# thrust_RP2040.net
KiCad netlist of a schematic drawn in Altium Designer
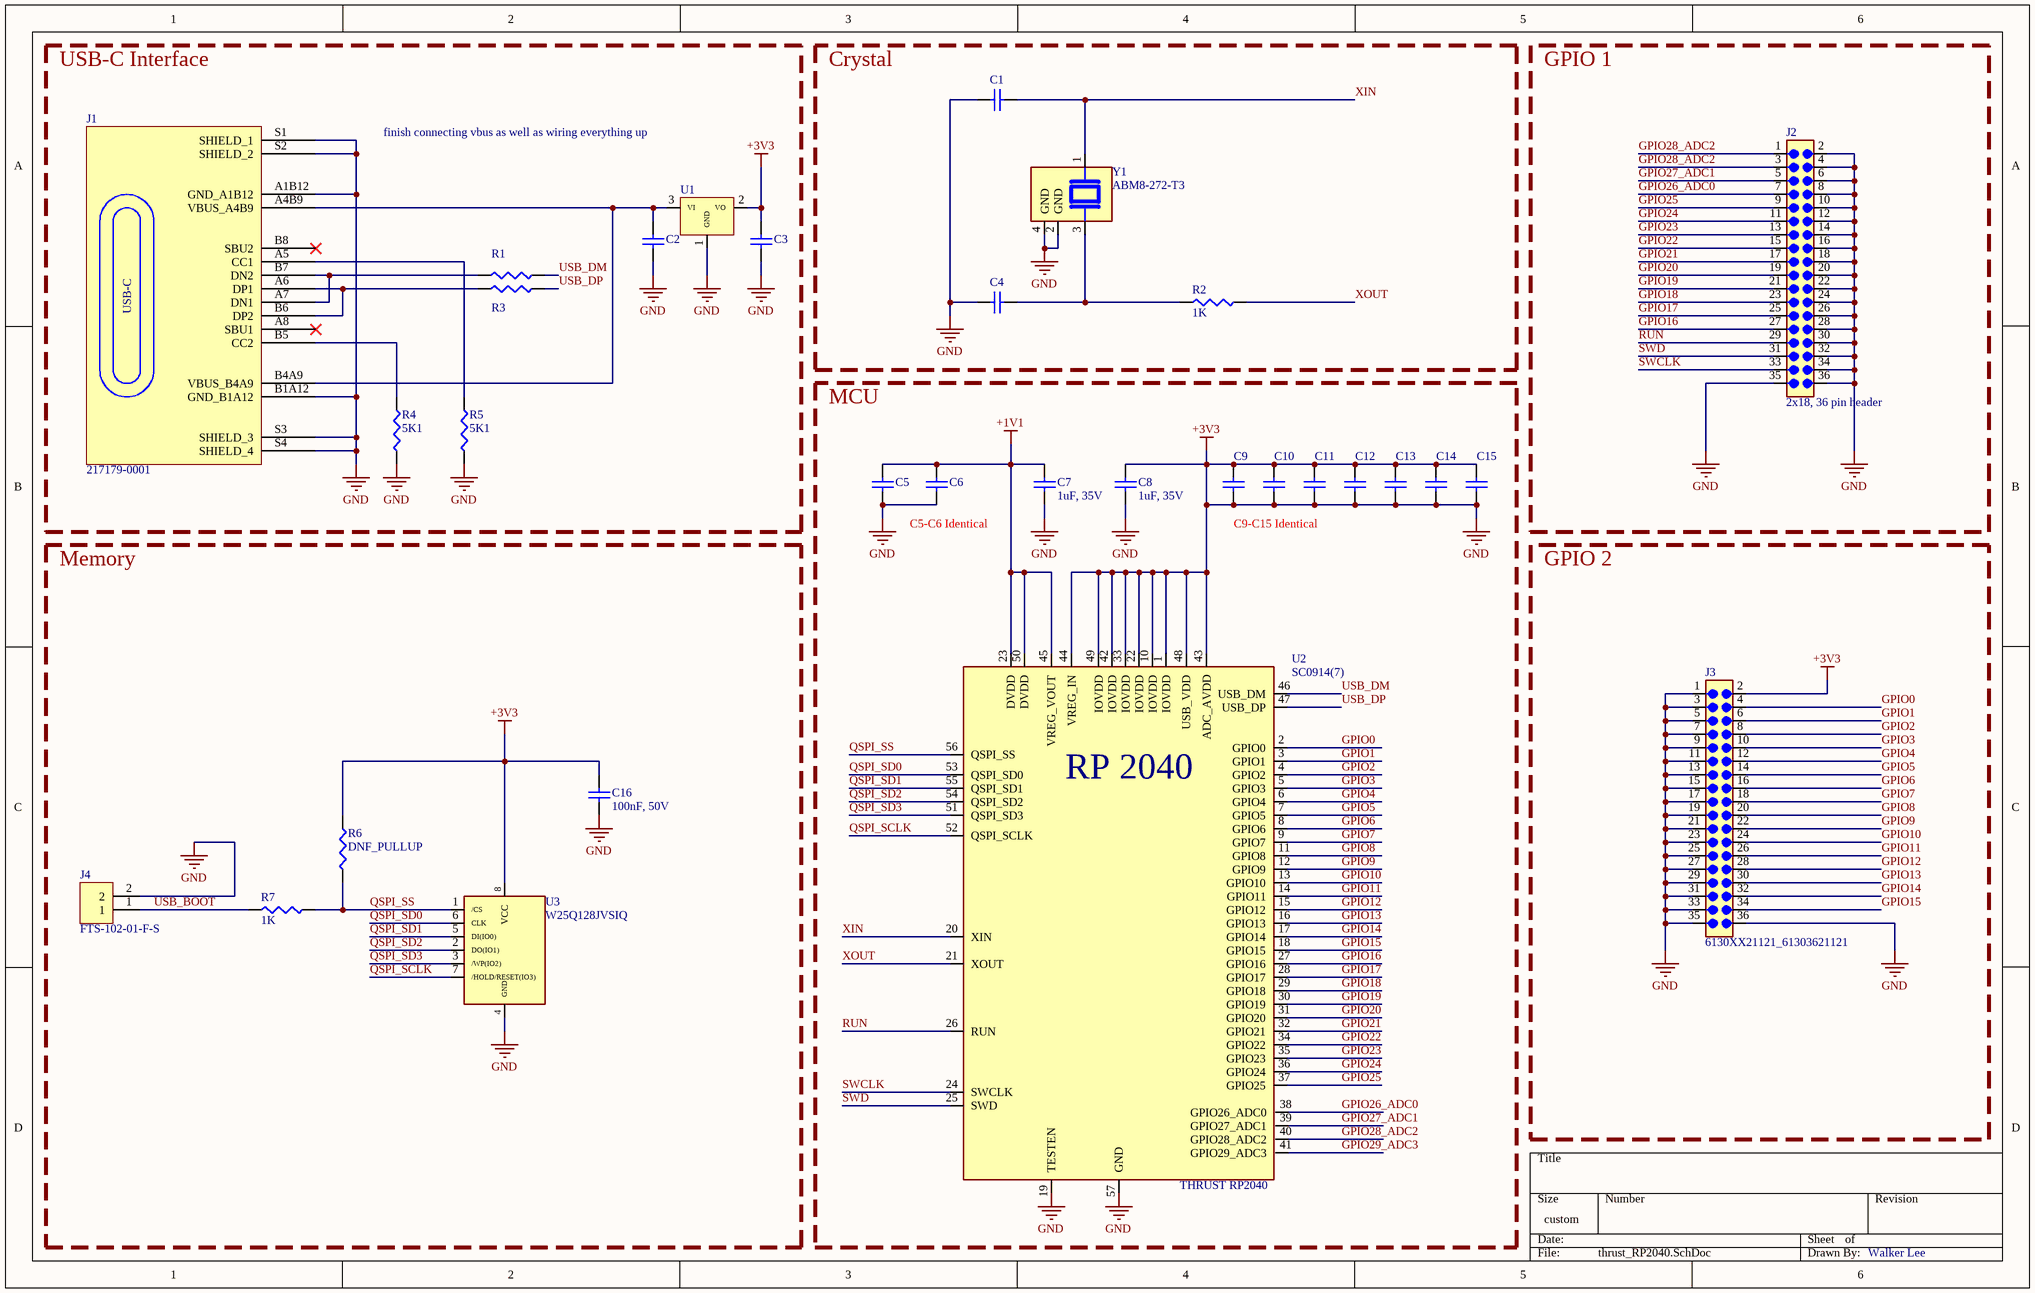
[diagram p0: thrust_RP2040.SchDoc]

(export (version "E")
  (design (tool "Eeschema 10.0.6"))
  (components
    (comp (ref "C1")
      (value "CL05C150JB5NNNC")
      (description "CAP CER 15PF 50V C0G/NP0 0402")
      (fields (field (name "MANUFACTURER") "Samsung Electro-Mechanics") (field (name "TOLERANCE") "5%"))
      (libsource (lib "thrust_obc") (part "CL05C150JB5NNNC"))
    )
    (comp (ref "C2")
      (value "10uF, 10V")
      (footprint "CAPC1005X55N")
      (description "CAP CER 10UF 10V X5R 0402")
      (fields
        (field (name "MANUFACTURER") "Samsung")
        (field (name "MANUFACTURER PART NUMBER") "CL05A106MP8NUB8")
      )
      (libsource (lib "thrust_obc") (part "CL05A106MP8NUB8"))
    )
    (comp (ref "C3")
      (value "10uF, 10V")
      (footprint "CAPC1005X55N")
      (description "CAP CER 10UF 10V X5R 0402")
      (fields
        (field (name "MANUFACTURER") "Samsung")
        (field (name "MANUFACTURER PART NUMBER") "CL05A106MP8NUB8")
      )
      (libsource (lib "thrust_obc") (part "CL05A106MP8NUB8"))
    )
    (comp (ref "C4")
      (value "CL05C150JB5NNNC")
      (description "CAP CER 15PF 50V C0G/NP0 0402")
      (fields (field (name "MANUFACTURER") "Samsung Electro-Mechanics") (field (name "TOLERANCE") "5%"))
      (libsource (lib "thrust_obc") (part "CL05C150JB5NNNC"))
    )
    (comp (ref "C5")
      (value "100nF, 50V")
      (footprint "CAPC1005X55N")
      (description "50V 100nF X7R 10% 0402 Multilayer Ceramic Capacitors MLCC - SMD/SMT ROHS")
      (fields
        (field (name "MANUFACTURER") "Samsung")
        (field (name "MANUFACTURER PART NUMBER") "CL05B104KB54PNC")
      )
      (libsource (lib "thrust_obc") (part "CL05B104KB54PNC"))
    )
    (comp (ref "C6")
      (value "100nF, 50V")
      (footprint "CAPC1005X55N")
      (description "50V 100nF X7R 10% 0402 Multilayer Ceramic Capacitors MLCC - SMD/SMT ROHS")
      (fields
        (field (name "MANUFACTURER") "Samsung")
        (field (name "MANUFACTURER PART NUMBER") "CL05B104KB54PNC")
      )
      (libsource (lib "thrust_obc") (part "CL05B104KB54PNC"))
    )
    (comp (ref "C7")
      (value "1uF, 35V")
      (footprint "CAPC1005X55N")
      (description "CAP CER 1UF 35V X5R 0402")
      (fields
        (field (name "MANUFACTURER") "Samsung")
        (field (name "MANUFACTURER PART NUMBER") "CL05A105KL5NRNC")
      )
      (libsource (lib "thrust_obc") (part "CL05A105KL5NRNC"))
    )
    (comp (ref "C8")
      (value "1uF, 35V")
      (footprint "CAPC1005X55N")
      (description "CAP CER 1UF 35V X5R 0402")
      (fields
        (field (name "MANUFACTURER") "Samsung")
        (field (name "MANUFACTURER PART NUMBER") "CL05A105KL5NRNC")
      )
      (libsource (lib "thrust_obc") (part "CL05A105KL5NRNC"))
    )
    (comp (ref "C9")
      (value "100nF, 50V")
      (footprint "CAPC1005X55N")
      (description "50V 100nF X7R 10% 0402 Multilayer Ceramic Capacitors MLCC - SMD/SMT ROHS")
      (fields
        (field (name "MANUFACTURER") "Samsung")
        (field (name "MANUFACTURER PART NUMBER") "CL05B104KB54PNC")
      )
      (libsource (lib "thrust_obc") (part "CL05B104KB54PNC"))
    )
    (comp (ref "C10")
      (value "100nF, 50V")
      (footprint "CAPC1005X55N")
      (description "50V 100nF X7R 10% 0402 Multilayer Ceramic Capacitors MLCC - SMD/SMT ROHS")
      (fields
        (field (name "MANUFACTURER") "Samsung")
        (field (name "MANUFACTURER PART NUMBER") "CL05B104KB54PNC")
      )
      (libsource (lib "thrust_obc") (part "CL05B104KB54PNC"))
    )
    (comp (ref "C11")
      (value "100nF, 50V")
      (footprint "CAPC1005X55N")
      (description "50V 100nF X7R 10% 0402 Multilayer Ceramic Capacitors MLCC - SMD/SMT ROHS")
      (fields
        (field (name "MANUFACTURER") "Samsung")
        (field (name "MANUFACTURER PART NUMBER") "CL05B104KB54PNC")
      )
      (libsource (lib "thrust_obc") (part "CL05B104KB54PNC"))
    )
    (comp (ref "C12")
      (value "100nF, 50V")
      (footprint "CAPC1005X55N")
      (description "50V 100nF X7R 10% 0402 Multilayer Ceramic Capacitors MLCC - SMD/SMT ROHS")
      (fields
        (field (name "MANUFACTURER") "Samsung")
        (field (name "MANUFACTURER PART NUMBER") "CL05B104KB54PNC")
      )
      (libsource (lib "thrust_obc") (part "CL05B104KB54PNC"))
    )
    (comp (ref "C13")
      (value "100nF, 50V")
      (footprint "CAPC1005X55N")
      (description "50V 100nF X7R 10% 0402 Multilayer Ceramic Capacitors MLCC - SMD/SMT ROHS")
      (fields
        (field (name "MANUFACTURER") "Samsung")
        (field (name "MANUFACTURER PART NUMBER") "CL05B104KB54PNC")
      )
      (libsource (lib "thrust_obc") (part "CL05B104KB54PNC"))
    )
    (comp (ref "C14")
      (value "100nF, 50V")
      (footprint "CAPC1005X55N")
      (description "50V 100nF X7R 10% 0402 Multilayer Ceramic Capacitors MLCC - SMD/SMT ROHS")
      (fields
        (field (name "MANUFACTURER") "Samsung")
        (field (name "MANUFACTURER PART NUMBER") "CL05B104KB54PNC")
      )
      (libsource (lib "thrust_obc") (part "CL05B104KB54PNC"))
    )
    (comp (ref "C15")
      (value "100nF, 50V")
      (footprint "CAPC1005X55N")
      (description "50V 100nF X7R 10% 0402 Multilayer Ceramic Capacitors MLCC - SMD/SMT ROHS")
      (fields
        (field (name "MANUFACTURER") "Samsung")
        (field (name "MANUFACTURER PART NUMBER") "CL05B104KB54PNC")
      )
      (libsource (lib "thrust_obc") (part "CL05B104KB54PNC"))
    )
    (comp (ref "C16")
      (value "100nF, 50V")
      (footprint "CAPC1005X55N")
      (description "50V 100nF X7R 10% 0402 Multilayer Ceramic Capacitors MLCC - SMD/SMT ROHS")
      (fields
        (field (name "MANUFACTURER") "Samsung")
        (field (name "MANUFACTURER PART NUMBER") "CL05B104KB54PNC")
      )
      (libsource (lib "thrust_obc") (part "CL05B104KB54PNC"))
    )
    (comp (ref "J1")
      (value "217179-0001")
      (footprint "FP-2171790001-MFG")
      (description "CONN RCP USB2.0 TYP C 24P SMD RA")
      (fields (field (name "MANUFACTURER") "Molex") (field (name "LCSC PART NUMBER") "C3197684"))
      (libsource (lib "thrust_obc") (part "217179-0001"))
    )
    (comp (ref "J2")
      (value "2x18, 36 pin header")
      (footprint "61303621121")
      (description "36 pins, dual Row , straight, gold plating")
      (fields (field (name "MF") "Wurth Electronics") (field (name "MP") "61303621121"))
      (libsource (lib "thrust_obc") (part "6130XX21121_61303621121"))
    )
    (comp (ref "J3")
      (value "6130XX21121_61303621121")
      (footprint "61303621121")
      (description "36 pins, dual Row , straight, gold plating")
      (fields (field (name "MF") "Wurth Electronics") (field (name "MP") "61303621121"))
      (libsource (lib "thrust_obc") (part "6130XX21121_61303621121"))
    )
    (comp (ref "J4")
      (value "FTS-102-01-F-S")
      (description "CONN HEADER VERT 2POS 1.27MM")
      (fields (field (name "MANUFACTURER") "Samtec") (field (name "LCSC PART NUMBER") "C6045317"))
      (libsource (lib "thrust_obc") (part "FTS-102-01-F-S"))
    )
    (comp (ref "R1")
      (value "27R")
      (footprint "RESC1005X37N")
      (description "RES 27 OHM 1% 1/16W 0402")
      (fields
        (field (name "MANUFACTURER") "Yageo")
        (field (name "MANUFACTURER PART NUMBER") "RC0402FR-0727RL")
      )
      (libsource (lib "thrust_obc") (part "RC0402FR-0727RL"))
    )
    (comp (ref "R2")
      (value "1K")
      (footprint "RESC1005X37N")
      (description "RES 1K OHM 1% 1/16W 0402")
      (fields
        (field (name "MANUFACTURER") "Yageo")
        (field (name "MANUFACTURER PART NUMBER") "RC0402FR-071KL")
      )
      (libsource (lib "thrust_obc") (part "RC0402FR-071KL"))
    )
    (comp (ref "R3")
      (value "27R")
      (footprint "RESC1005X37N")
      (description "RES 27 OHM 1% 1/16W 0402")
      (fields
        (field (name "MANUFACTURER") "Yageo")
        (field (name "MANUFACTURER PART NUMBER") "RC0402FR-0727RL")
      )
      (libsource (lib "thrust_obc") (part "RC0402FR-0727RL"))
    )
    (comp (ref "R4")
      (value "5K1")
      (footprint "RESC1005X37N")
      (description "RES SMD 5.1K OHM 1% 1/16W 0402")
      (fields
        (field (name "MANUFACTURER") "Yageo")
        (field (name "MANUFACTURER PART NUMBER") "AC0402FR-075K1L")
      )
      (libsource (lib "thrust_obc") (part "AC0402FR-075K1L"))
    )
    (comp (ref "R5")
      (value "5K1")
      (footprint "RESC1005X37N")
      (description "RES SMD 5.1K OHM 1% 1/16W 0402")
      (fields
        (field (name "MANUFACTURER") "Yageo")
        (field (name "MANUFACTURER PART NUMBER") "AC0402FR-075K1L")
      )
      (libsource (lib "thrust_obc") (part "AC0402FR-075K1L"))
    )
    (comp (ref "R6")
      (value "DNF_PULLUP")
      (footprint "RESC1005X37N")
      (description "Generic 0402 Resistor - DO NOT POPULATE")
      (fields
        (field (name "MANUFACTURER") "Yageo")
        (field (name "MANUFACTURER PART NUMBER") "RC0402FR-071KL")
      )
      (libsource (lib "thrust_obc") (part "RC0402FR-071KL_1"))
    )
    (comp (ref "R7")
      (value "1K")
      (footprint "RESC1005X37N")
      (description "RES 1K OHM 1% 1/16W 0402")
      (fields
        (field (name "MANUFACTURER") "Yageo")
        (field (name "MANUFACTURER PART NUMBER") "RC0402FR-071KL")
      )
      (libsource (lib "thrust_obc") (part "RC0402FR-071KL"))
    )
    (comp (ref "U1")
      (value "NCP1117ST33T3G")
      (description "IC REG LINEAR 3.3V 1A SOT-223")
      (fields (field (name "MANUFACTURER") "onsemi") (field (name "TOLERANCE") "1%"))
      (libsource (lib "thrust_obc") (part "NCP1117ST33T3G"))
    )
    (comp (ref "U2")
      (value "SC0914(7)")
      (description "RISC Microcontroller, FLASH, Cortex-M0+ CPU, 133MHz, CMOS")
      (fields (field (name "MANUFACTURER") "Raspberry Pi") (field (name "LCSC PART NUMBER") "C6472266"))
      (libsource (lib "thrust_obc") (part "SC0914(7)"))
    )
    (comp (ref "U3")
      (value "W25Q128JVSIQ")
      (footprint "SOIC127P790X216-8N")
      (description "FLASH - NOR Memory IC 128Mb (16M x 8) SPI - Quad I/O, QPI, DTR 133 MHz 8-SOIC")
      (fields (field (name "MF") "Winbond Electronics") (field (name "LCSC PART NUMBER") "C97521"))
      (libsource (lib "thrust_obc") (part "W25Q128JVSIQ"))
    )
    (comp (ref "Y1")
      (value "ABM8-272-T3")
      (footprint "XTAL_ABM8-272-T3")
      (description "12 MHz Â±30ppm Crystal 10pF 50 Ohms 4-SMD, No Lead")
      (fields (field (name "MF") "ABRACON") (field (name "LCSC PART NUMBER") "C20625731"))
      (libsource (lib "thrust_obc") (part "ABM8-272-T3"))
    )
  )
  (nets
    (net (code "1") (name "+1V1") (class "Default")
      (node (ref "C5") (pin "2") (pinfunction "2_2") (pintype "passive"))
      (node (ref "C6") (pin "2") (pinfunction "2_2") (pintype "passive"))
      (node (ref "C7") (pin "2") (pinfunction "2_2") (pintype "passive"))
      (node (ref "U2") (pin "23") (pinfunction "DVDD_23") (pintype "passive"))
      (node (ref "U2") (pin "45") (pinfunction "VREG_VOUT_45") (pintype "passive"))
      (node (ref "U2") (pin "50") (pinfunction "DVDD_50") (pintype "passive"))
    )
    (net (code "2") (name "+3V3") (class "Default")
      (node (ref "C1") (pin "1") (pinfunction "1_1") (pintype "passive"))
      (node (ref "C10") (pin "1") (pinfunction "1_1") (pintype "passive"))
      (node (ref "C10") (pin "2") (pinfunction "2_2") (pintype "passive"))
      (node (ref "C11") (pin "1") (pinfunction "1_1") (pintype "passive"))
      (node (ref "C11") (pin "2") (pinfunction "2_2") (pintype "passive"))
      (node (ref "C12") (pin "1") (pinfunction "1_1") (pintype "passive"))
      (node (ref "C12") (pin "2") (pinfunction "2_2") (pintype "passive"))
      (node (ref "C13") (pin "1") (pinfunction "1_1") (pintype "passive"))
      (node (ref "C13") (pin "2") (pinfunction "2_2") (pintype "passive"))
      (node (ref "C14") (pin "1") (pinfunction "1_1") (pintype "passive"))
      (node (ref "C14") (pin "2") (pinfunction "2_2") (pintype "passive"))
      (node (ref "C15") (pin "1") (pinfunction "1_1") (pintype "passive"))
      (node (ref "C15") (pin "2") (pinfunction "2_2") (pintype "passive"))
      (node (ref "C16") (pin "1") (pinfunction "1_1") (pintype "passive"))
      (node (ref "C16") (pin "2") (pinfunction "2_2") (pintype "passive"))
      (node (ref "C2") (pin "1") (pinfunction "1_1") (pintype "passive"))
      (node (ref "C3") (pin "1") (pinfunction "1_1") (pintype "passive"))
      (node (ref "C3") (pin "2") (pinfunction "2_2") (pintype "passive"))
      (node (ref "C4") (pin "1") (pinfunction "1_1") (pintype "passive"))
      (node (ref "C5") (pin "1") (pinfunction "1_1") (pintype "passive"))
      (node (ref "C6") (pin "1") (pinfunction "1_1") (pintype "passive"))
      (node (ref "C7") (pin "1") (pinfunction "1_1") (pintype "passive"))
      (node (ref "C8") (pin "1") (pinfunction "1_1") (pintype "passive"))
      (node (ref "C8") (pin "2") (pinfunction "2_2") (pintype "passive"))
      (node (ref "C9") (pin "1") (pinfunction "1_1") (pintype "passive"))
      (node (ref "C9") (pin "2") (pinfunction "2_2") (pintype "passive"))
      (node (ref "J1") (pin "A1B12") (pinfunction "GND_A1B12_A1B12") (pintype "passive"))
      (node (ref "J1") (pin "B1A12") (pinfunction "GND_B1A12_B1A12") (pintype "passive"))
      (node (ref "J1") (pin "S1") (pinfunction "SHIELD_1_S1") (pintype "passive"))
      (node (ref "J1") (pin "S2") (pinfunction "SHIELD_2_S2") (pintype "passive"))
      (node (ref "J1") (pin "S3") (pinfunction "SHIELD_3_S3") (pintype "passive"))
      (node (ref "J1") (pin "S4") (pinfunction "SHIELD_4_S4") (pintype "passive"))
      (node (ref "J2") (pin "10") (pinfunction "10_10") (pintype "passive"))
      (node (ref "J2") (pin "12") (pinfunction "12_12") (pintype "passive"))
      (node (ref "J2") (pin "14") (pinfunction "14_14") (pintype "passive"))
      (node (ref "J2") (pin "16") (pinfunction "16_16") (pintype "passive"))
      (node (ref "J2") (pin "18") (pinfunction "18_18") (pintype "passive"))
      (node (ref "J2") (pin "2") (pinfunction "2_2") (pintype "passive"))
      (node (ref "J2") (pin "20") (pinfunction "20_20") (pintype "passive"))
      (node (ref "J2") (pin "22") (pinfunction "22_22") (pintype "passive"))
      (node (ref "J2") (pin "24") (pinfunction "24_24") (pintype "passive"))
      (node (ref "J2") (pin "26") (pinfunction "26_26") (pintype "passive"))
      (node (ref "J2") (pin "28") (pinfunction "28_28") (pintype "passive"))
      (node (ref "J2") (pin "30") (pinfunction "30_30") (pintype "passive"))
      (node (ref "J2") (pin "32") (pinfunction "32_32") (pintype "passive"))
      (node (ref "J2") (pin "34") (pinfunction "34_34") (pintype "passive"))
      (node (ref "J2") (pin "35") (pinfunction "35_35") (pintype "passive"))
      (node (ref "J2") (pin "36") (pinfunction "36_36") (pintype "passive"))
      (node (ref "J2") (pin "4") (pinfunction "4_4") (pintype "passive"))
      (node (ref "J2") (pin "6") (pinfunction "6_6") (pintype "passive"))
      (node (ref "J2") (pin "8") (pinfunction "8_8") (pintype "passive"))
      (node (ref "J3") (pin "1") (pinfunction "1_1") (pintype "passive"))
      (node (ref "J3") (pin "11") (pinfunction "11_11") (pintype "passive"))
      (node (ref "J3") (pin "13") (pinfunction "13_13") (pintype "passive"))
      (node (ref "J3") (pin "15") (pinfunction "15_15") (pintype "passive"))
      (node (ref "J3") (pin "17") (pinfunction "17_17") (pintype "passive"))
      (node (ref "J3") (pin "19") (pinfunction "19_19") (pintype "passive"))
      (node (ref "J3") (pin "2") (pinfunction "2_2") (pintype "passive"))
      (node (ref "J3") (pin "21") (pinfunction "21_21") (pintype "passive"))
      (node (ref "J3") (pin "23") (pinfunction "23_23") (pintype "passive"))
      (node (ref "J3") (pin "25") (pinfunction "25_25") (pintype "passive"))
      (node (ref "J3") (pin "27") (pinfunction "27_27") (pintype "passive"))
      (node (ref "J3") (pin "29") (pinfunction "29_29") (pintype "passive"))
      (node (ref "J3") (pin "3") (pinfunction "3_3") (pintype "passive"))
      (node (ref "J3") (pin "31") (pinfunction "31_31") (pintype "passive"))
      (node (ref "J3") (pin "33") (pinfunction "33_33") (pintype "passive"))
      (node (ref "J3") (pin "35") (pinfunction "35_35") (pintype "passive"))
      (node (ref "J3") (pin "36") (pinfunction "36_36") (pintype "passive"))
      (node (ref "J3") (pin "5") (pinfunction "5_5") (pintype "passive"))
      (node (ref "J3") (pin "7") (pinfunction "7_7") (pintype "passive"))
      (node (ref "J3") (pin "9") (pinfunction "9_9") (pintype "passive"))
      (node (ref "J4") (pin "2") (pinfunction "2_2") (pintype "passive"))
      (node (ref "R4") (pin "1") (pinfunction "1_1") (pintype "passive"))
      (node (ref "R5") (pin "1") (pinfunction "1_1") (pintype "passive"))
      (node (ref "R6") (pin "2") (pinfunction "2_2") (pintype "passive"))
      (node (ref "U1") (pin "1") (pinfunction "GND_1") (pintype "passive"))
      (node (ref "U1") (pin "2") (pinfunction "VO_2") (pintype "passive"))
      (node (ref "U2") (pin "1") (pinfunction "IOVDD_1") (pintype "passive"))
      (node (ref "U2") (pin "10") (pinfunction "IOVDD_10") (pintype "passive"))
      (node (ref "U2") (pin "19") (pinfunction "TESTEN_19") (pintype "passive"))
      (node (ref "U2") (pin "22") (pinfunction "IOVDD_22") (pintype "passive"))
      (node (ref "U2") (pin "33") (pinfunction "IOVDD_33") (pintype "passive"))
      (node (ref "U2") (pin "42") (pinfunction "IOVDD_42") (pintype "passive"))
      (node (ref "U2") (pin "43") (pinfunction "ADC_AVDD_43") (pintype "passive"))
      (node (ref "U2") (pin "44") (pinfunction "VREG_IN_44") (pintype "passive"))
      (node (ref "U2") (pin "48") (pinfunction "USB_VDD_48") (pintype "passive"))
      (node (ref "U2") (pin "49") (pinfunction "IOVDD_49") (pintype "passive"))
      (node (ref "U2") (pin "57") (pinfunction "GND_57") (pintype "passive"))
      (node (ref "U3") (pin "4") (pinfunction "GND_4") (pintype "power_in"))
      (node (ref "U3") (pin "8") (pinfunction "VCC_8") (pintype "power_in"))
      (node (ref "Y1") (pin "2") (pinfunction "GND_2") (pintype "power_in"))
      (node (ref "Y1") (pin "4") (pinfunction "GND_4") (pintype "power_in"))
    )
    (net (code "3") (name "/GPIO0") (class "Default")
      (node (ref "J3") (pin "4") (pinfunction "4_4") (pintype "passive"))
      (node (ref "U2") (pin "2") (pinfunction "GPIO0_2") (pintype "passive"))
    )
    (net (code "4") (name "/GPIO1") (class "Default")
      (node (ref "J3") (pin "6") (pinfunction "6_6") (pintype "passive"))
      (node (ref "U2") (pin "3") (pinfunction "GPIO1_3") (pintype "passive"))
    )
    (net (code "5") (name "/GPIO2") (class "Default")
      (node (ref "J3") (pin "8") (pinfunction "8_8") (pintype "passive"))
      (node (ref "U2") (pin "4") (pinfunction "GPIO2_4") (pintype "passive"))
    )
    (net (code "6") (name "/GPIO3") (class "Default")
      (node (ref "J3") (pin "10") (pinfunction "10_10") (pintype "passive"))
      (node (ref "U2") (pin "5") (pinfunction "GPIO3_5") (pintype "passive"))
    )
    (net (code "7") (name "/GPIO4") (class "Default")
      (node (ref "J3") (pin "12") (pinfunction "12_12") (pintype "passive"))
      (node (ref "U2") (pin "6") (pinfunction "GPIO4_6") (pintype "passive"))
    )
    (net (code "8") (name "/GPIO5") (class "Default")
      (node (ref "J3") (pin "14") (pinfunction "14_14") (pintype "passive"))
      (node (ref "U2") (pin "7") (pinfunction "GPIO5_7") (pintype "passive"))
    )
    (net (code "9") (name "/GPIO6") (class "Default")
      (node (ref "J3") (pin "16") (pinfunction "16_16") (pintype "passive"))
      (node (ref "U2") (pin "8") (pinfunction "GPIO6_8") (pintype "passive"))
    )
    (net (code "10") (name "/GPIO7") (class "Default")
      (node (ref "J3") (pin "18") (pinfunction "18_18") (pintype "passive"))
      (node (ref "U2") (pin "9") (pinfunction "GPIO7_9") (pintype "passive"))
    )
    (net (code "11") (name "/GPIO8") (class "Default")
      (node (ref "J3") (pin "20") (pinfunction "20_20") (pintype "passive"))
      (node (ref "U2") (pin "11") (pinfunction "GPIO8_11") (pintype "passive"))
    )
    (net (code "12") (name "/GPIO9") (class "Default")
      (node (ref "J3") (pin "22") (pinfunction "22_22") (pintype "passive"))
      (node (ref "U2") (pin "12") (pinfunction "GPIO9_12") (pintype "passive"))
    )
    (net (code "13") (name "/GPIO10") (class "Default")
      (node (ref "J3") (pin "24") (pinfunction "24_24") (pintype "passive"))
      (node (ref "U2") (pin "13") (pinfunction "GPIO10_13") (pintype "passive"))
    )
    (net (code "14") (name "/GPIO11") (class "Default")
      (node (ref "J3") (pin "26") (pinfunction "26_26") (pintype "passive"))
      (node (ref "U2") (pin "14") (pinfunction "GPIO11_14") (pintype "passive"))
    )
    (net (code "15") (name "/GPIO12") (class "Default")
      (node (ref "J3") (pin "28") (pinfunction "28_28") (pintype "passive"))
      (node (ref "U2") (pin "15") (pinfunction "GPIO12_15") (pintype "passive"))
    )
    (net (code "16") (name "/GPIO13") (class "Default")
      (node (ref "J3") (pin "30") (pinfunction "30_30") (pintype "passive"))
      (node (ref "U2") (pin "16") (pinfunction "GPIO13_16") (pintype "passive"))
    )
    (net (code "17") (name "/GPIO14") (class "Default")
      (node (ref "J3") (pin "32") (pinfunction "32_32") (pintype "passive"))
      (node (ref "U2") (pin "17") (pinfunction "GPIO14_17") (pintype "passive"))
    )
    (net (code "18") (name "/GPIO15") (class "Default")
      (node (ref "J3") (pin "34") (pinfunction "34_34") (pintype "passive"))
      (node (ref "U2") (pin "18") (pinfunction "GPIO15_18") (pintype "passive"))
    )
    (net (code "19") (name "/GPIO16") (class "Default")
      (node (ref "J2") (pin "27") (pinfunction "27_27") (pintype "passive"))
      (node (ref "U2") (pin "27") (pinfunction "GPIO16_27") (pintype "passive"))
    )
    (net (code "20") (name "/GPIO17") (class "Default")
      (node (ref "J2") (pin "25") (pinfunction "25_25") (pintype "passive"))
      (node (ref "U2") (pin "28") (pinfunction "GPIO17_28") (pintype "passive"))
    )
    (net (code "21") (name "/GPIO18") (class "Default")
      (node (ref "J2") (pin "23") (pinfunction "23_23") (pintype "passive"))
      (node (ref "U2") (pin "29") (pinfunction "GPIO18_29") (pintype "passive"))
    )
    (net (code "22") (name "/GPIO19") (class "Default")
      (node (ref "J2") (pin "21") (pinfunction "21_21") (pintype "passive"))
      (node (ref "U2") (pin "30") (pinfunction "GPIO19_30") (pintype "passive"))
    )
    (net (code "23") (name "/GPIO20") (class "Default")
      (node (ref "J2") (pin "19") (pinfunction "19_19") (pintype "passive"))
      (node (ref "U2") (pin "31") (pinfunction "GPIO20_31") (pintype "passive"))
    )
    (net (code "24") (name "/GPIO21") (class "Default")
      (node (ref "J2") (pin "17") (pinfunction "17_17") (pintype "passive"))
      (node (ref "U2") (pin "32") (pinfunction "GPIO21_32") (pintype "passive"))
    )
    (net (code "25") (name "/GPIO22") (class "Default")
      (node (ref "J2") (pin "15") (pinfunction "15_15") (pintype "passive"))
      (node (ref "U2") (pin "34") (pinfunction "GPIO22_34") (pintype "passive"))
    )
    (net (code "26") (name "/GPIO23") (class "Default")
      (node (ref "J2") (pin "13") (pinfunction "13_13") (pintype "passive"))
      (node (ref "U2") (pin "35") (pinfunction "GPIO23_35") (pintype "passive"))
    )
    (net (code "27") (name "/GPIO24") (class "Default")
      (node (ref "J2") (pin "11") (pinfunction "11_11") (pintype "passive"))
      (node (ref "U2") (pin "36") (pinfunction "GPIO24_36") (pintype "passive"))
    )
    (net (code "28") (name "/GPIO25") (class "Default")
      (node (ref "J2") (pin "9") (pinfunction "9_9") (pintype "passive"))
      (node (ref "U2") (pin "37") (pinfunction "GPIO25_37") (pintype "passive"))
    )
    (net (code "29") (name "/GPIO26_ADC0") (class "Default")
      (node (ref "J2") (pin "7") (pinfunction "7_7") (pintype "passive"))
      (node (ref "U2") (pin "38") (pinfunction "GPIO26_ADC0_38") (pintype "passive"))
    )
    (net (code "30") (name "/GPIO27_ADC1") (class "Default")
      (node (ref "J2") (pin "5") (pinfunction "5_5") (pintype "passive"))
      (node (ref "U2") (pin "39") (pinfunction "GPIO27_ADC1_39") (pintype "passive"))
    )
    (net (code "31") (name "/GPIO28_ADC2") (class "Default")
      (node (ref "J2") (pin "1") (pinfunction "1_1") (pintype "passive"))
      (node (ref "J2") (pin "3") (pinfunction "3_3") (pintype "passive"))
      (node (ref "U2") (pin "40") (pinfunction "GPIO28_ADC2_40") (pintype "passive"))
    )
    (net (code "32") (name "/GPIO29_ADC3") (class "Default")
      (node (ref "U2") (pin "41") (pinfunction "GPIO29_ADC3_41") (pintype "passive"))
    )
    (net (code "33") (name "/QSPI_SCLK") (class "Default")
      (node (ref "U2") (pin "52") (pinfunction "QSPI_SCLK_52") (pintype "passive"))
      (node (ref "U3") (pin "7") (pinfunction "/HOLD/RESET(IO3)_7") (pintype "open_collector"))
    )
    (net (code "34") (name "/QSPI_SD0") (class "Default")
      (node (ref "U2") (pin "53") (pinfunction "QSPI_SD0_53") (pintype "passive"))
      (node (ref "U3") (pin "6") (pinfunction "CLK_6") (pintype "passive"))
    )
    (net (code "35") (name "/QSPI_SD1") (class "Default")
      (node (ref "U2") (pin "55") (pinfunction "QSPI_SD1_55") (pintype "passive"))
      (node (ref "U3") (pin "5") (pinfunction "DI(IO0)_5") (pintype "open_collector"))
    )
    (net (code "36") (name "/QSPI_SD2") (class "Default")
      (node (ref "U2") (pin "54") (pinfunction "QSPI_SD2_54") (pintype "passive"))
      (node (ref "U3") (pin "2") (pinfunction "DO(IO1)_2") (pintype "open_collector"))
    )
    (net (code "37") (name "/QSPI_SD3") (class "Default")
      (node (ref "U2") (pin "51") (pinfunction "QSPI_SD3_51") (pintype "passive"))
      (node (ref "U3") (pin "3") (pinfunction "/WP(IO2)_3") (pintype "open_collector"))
    )
    (net (code "38") (name "/QSPI_SS") (class "Default")
      (node (ref "R6") (pin "1") (pinfunction "1_1") (pintype "passive"))
      (node (ref "R7") (pin "2") (pinfunction "2_2") (pintype "passive"))
      (node (ref "U2") (pin "56") (pinfunction "QSPI_SS_56") (pintype "passive"))
      (node (ref "U3") (pin "1") (pinfunction "/CS_1") (pintype "passive"))
    )
    (net (code "39") (name "/RUN") (class "Default")
      (node (ref "J2") (pin "29") (pinfunction "29_29") (pintype "passive"))
      (node (ref "U2") (pin "26") (pinfunction "RUN_26") (pintype "passive"))
    )
    (net (code "40") (name "/SWCLK") (class "Default")
      (node (ref "J2") (pin "33") (pinfunction "33_33") (pintype "passive"))
      (node (ref "U2") (pin "24") (pinfunction "SWCLK_24") (pintype "passive"))
    )
    (net (code "41") (name "/SWD") (class "Default")
      (node (ref "J2") (pin "31") (pinfunction "31_31") (pintype "passive"))
      (node (ref "U2") (pin "25") (pinfunction "SWD_25") (pintype "passive"))
    )
    (net (code "42") (name "/USB_DM") (class "Default")
      (node (ref "R1") (pin "2") (pinfunction "2_2") (pintype "passive"))
      (node (ref "U2") (pin "46") (pinfunction "USB_DM_46") (pintype "passive"))
    )
    (net (code "43") (name "/USB_DP") (class "Default")
      (node (ref "R3") (pin "2") (pinfunction "2_2") (pintype "passive"))
      (node (ref "U2") (pin "47") (pinfunction "USB_DP_47") (pintype "passive"))
    )
    (net (code "44") (name "/XIN") (class "Default")
      (node (ref "C1") (pin "2") (pinfunction "2_2") (pintype "passive"))
      (node (ref "U2") (pin "20") (pinfunction "XIN_20") (pintype "passive"))
      (node (ref "Y1") (pin "1") (pinfunction "1_1") (pintype "passive"))
    )
    (net (code "45") (name "/XOUT") (class "Default")
      (node (ref "R2") (pin "2") (pinfunction "2_2") (pintype "passive"))
      (node (ref "U2") (pin "21") (pinfunction "XOUT_21") (pintype "passive"))
    )
    (net (code "46") (name "/~{USB_BOOT}") (class "Default")
      (node (ref "J4") (pin "1") (pinfunction "1_1") (pintype "passive"))
      (node (ref "R7") (pin "1") (pinfunction "1_1") (pintype "passive"))
    )
    (net (code "47") (name "Net-(C4-Pad2)") (class "Default")
      (node (ref "C4") (pin "2") (pinfunction "2_2") (pintype "passive"))
      (node (ref "R2") (pin "1") (pinfunction "1_1") (pintype "passive"))
      (node (ref "Y1") (pin "3") (pinfunction "3_3") (pintype "passive"))
    )
    (net (code "48") (name "Net-(J1-CC1)") (class "Default")
      (node (ref "J1") (pin "A5") (pinfunction "CC1_A5") (pintype "passive"))
      (node (ref "R5") (pin "2") (pinfunction "2_2") (pintype "passive"))
    )
    (net (code "49") (name "Net-(J1-CC2)") (class "Default")
      (node (ref "J1") (pin "B5") (pinfunction "CC2_B5") (pintype "passive"))
      (node (ref "R4") (pin "2") (pinfunction "2_2") (pintype "passive"))
    )
    (net (code "50") (name "Net-(J1-DN1)") (class "Default")
      (node (ref "J1") (pin "A7") (pinfunction "DN1_A7") (pintype "passive"))
      (node (ref "J1") (pin "B7") (pinfunction "DN2_B7") (pintype "passive"))
      (node (ref "R1") (pin "1") (pinfunction "1_1") (pintype "passive"))
    )
    (net (code "51") (name "Net-(J1-DP1)") (class "Default")
      (node (ref "J1") (pin "A6") (pinfunction "DP1_A6") (pintype "passive"))
      (node (ref "J1") (pin "B6") (pinfunction "DP2_B6") (pintype "passive"))
      (node (ref "R3") (pin "1") (pinfunction "1_1") (pintype "passive"))
    )
    (net (code "52") (name "Net-(J1-VBUS_A4B9)") (class "Default")
      (node (ref "C2") (pin "2") (pinfunction "2_2") (pintype "passive"))
      (node (ref "J1") (pin "A4B9") (pinfunction "VBUS_A4B9_A4B9") (pintype "passive"))
      (node (ref "J1") (pin "B4A9") (pinfunction "VBUS_B4A9_B4A9") (pintype "passive"))
      (node (ref "U1") (pin "3") (pinfunction "VI_3") (pintype "passive"))
    )
    (net (code "53") (name "unconnected-(J1-SBU1-PadA8)") (class "Default")
      (node (ref "J1") (pin "A8") (pinfunction "SBU1_A8") (pintype "passive+no_connect"))
    )
    (net (code "54") (name "unconnected-(J1-SBU2-PadB8)") (class "Default")
      (node (ref "J1") (pin "B8") (pinfunction "SBU2_B8") (pintype "passive+no_connect"))
    )
  )
)
